# STMF1.net
KiCad netlist of a schematic drawn in Altium Designer
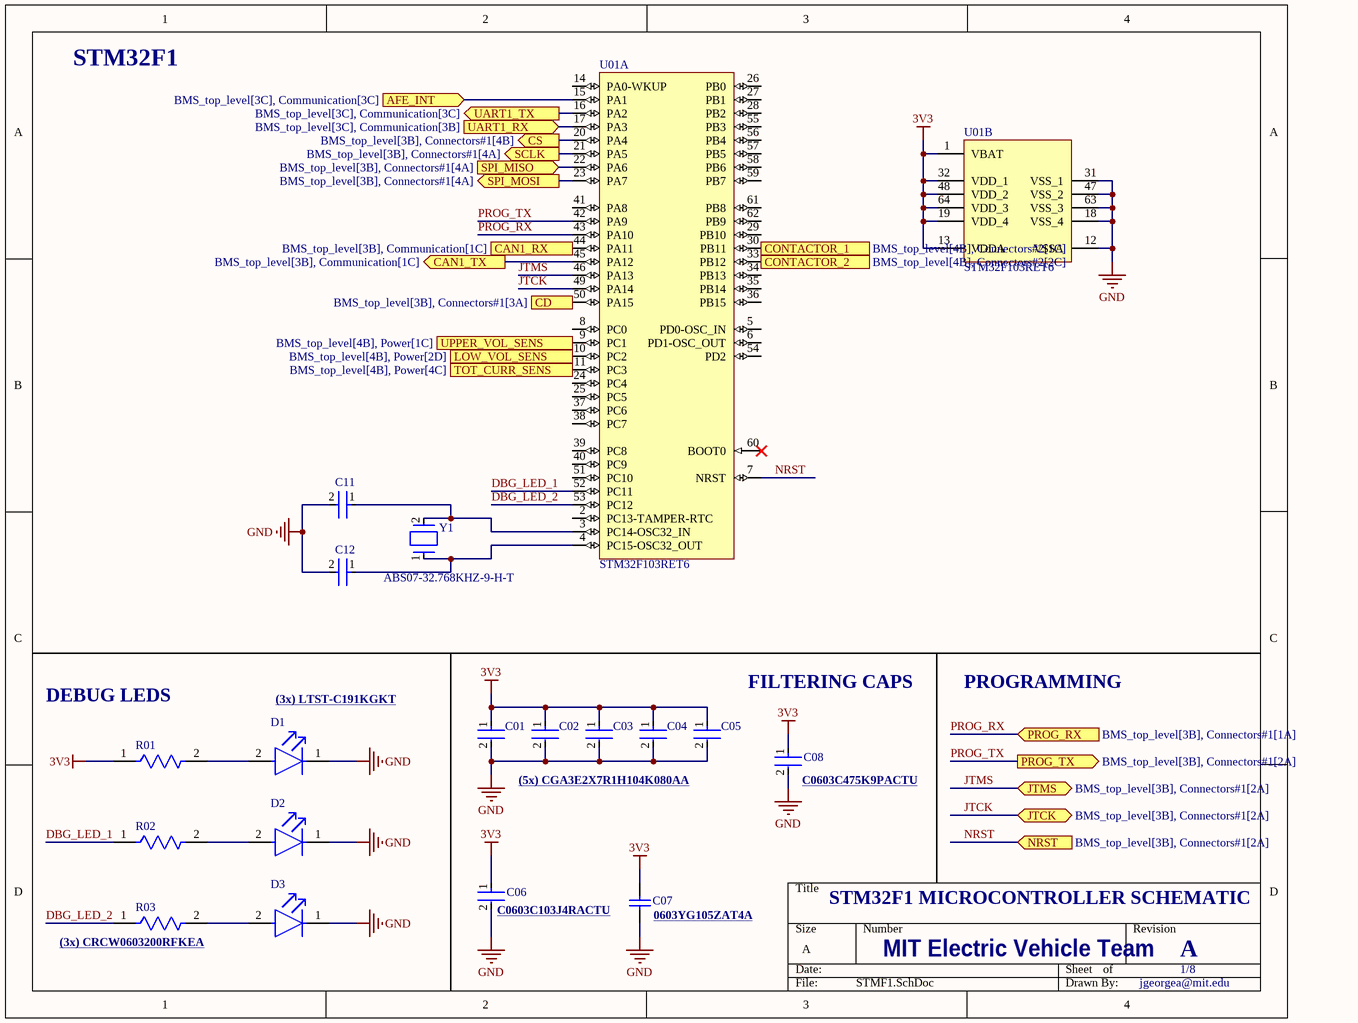
[diagram p0: STMF1.SchDoc]

(export (version "E")
  (design (tool "Eeschema 10.0.6"))
  (components
    (comp (ref "C01")
      (value "CGA3E2X7R1H104K080AA")
      (footprint "FP-CGA3E-0_3-0_1-IPC_A")
      (description "Cap Ceramic 100nF 50V X7R 10% Pad SMD 0603 +125°C Automotive T/R")
      (fields (field (name "TOLERANCE") "10%") (field (name "VOLTAGE") "50V"))
      (libsource (lib "Altium Content Vault") (part "b4654b650e69147ec39a6b967a45e02"))
    )
    (comp (ref "C02")
      (value "CGA3E2X7R1H104K080AA")
      (footprint "FP-CGA3E-0_3-0_1-IPC_A")
      (description "Cap Ceramic 100nF 50V X7R 10% Pad SMD 0603 +125°C Automotive T/R")
      (fields (field (name "TOLERANCE") "10%") (field (name "VOLTAGE") "50V"))
      (libsource (lib "Altium Content Vault") (part "b4654b650e69147ec39a6b967a45e02"))
    )
    (comp (ref "C03")
      (value "CGA3E2X7R1H104K080AA")
      (footprint "FP-CGA3E-0_3-0_1-IPC_A")
      (description "Cap Ceramic 100nF 50V X7R 10% Pad SMD 0603 +125°C Automotive T/R")
      (fields (field (name "TOLERANCE") "10%") (field (name "VOLTAGE") "50V"))
      (libsource (lib "Altium Content Vault") (part "b4654b650e69147ec39a6b967a45e02"))
    )
    (comp (ref "C04")
      (value "CGA3E2X7R1H104K080AA")
      (footprint "FP-CGA3E-0_3-0_1-IPC_A")
      (description "Cap Ceramic 100nF 50V X7R 10% Pad SMD 0603 +125°C Automotive T/R")
      (fields (field (name "TOLERANCE") "10%") (field (name "VOLTAGE") "50V"))
      (libsource (lib "Altium Content Vault") (part "b4654b650e69147ec39a6b967a45e02"))
    )
    (comp (ref "C05")
      (value "CGA3E2X7R1H104K080AA")
      (footprint "FP-CGA3E-0_3-0_1-IPC_A")
      (description "Cap Ceramic 100nF 50V X7R 10% Pad SMD 0603 +125°C Automotive T/R")
      (fields (field (name "TOLERANCE") "10%") (field (name "VOLTAGE") "50V"))
      (libsource (lib "Altium Content Vault") (part "b4654b650e69147ec39a6b967a45e02"))
    )
    (comp (ref "C06")
      (value "C0603C103J4RACTU")
      (footprint "FP-C0603C-CF-MFG")
      (description "CAP CER 10000PF 16V 5% X7R 0603")
      (fields (field (name "TOLERANCE") "0.05") (field (name "MANUFACTURER") "KEMET"))
      (libsource (lib "Altium Content Vault") (part "b4654b650e69147ec39a6b967a45e02"))
    )
    (comp (ref "C07")
      (value "0603YG105ZAT4A")
      (footprint "CAPC1608X90X35ML15T15")
      (fields (field (name "MANUFACTURER") "AVX Interconnect / Elco"))
      (libsource (lib "Altium Content Vault") (part "CAP"))
    )
    (comp (ref "C08")
      (value "C0603C475K9PACTU")
      (footprint "FP-C0603-CG-MFG")
      (description "CAP CER 4.7UF 6.3V X5R 0603")
      (fields (field (name "TOLERANCE") "10%") (field (name "MANUFACTURER") "Kemet"))
      (libsource (lib "Altium Content Vault") (part "11868f565c42a9108669ba33697ecf6"))
    )
    (comp (ref "C11")
      (value "CBR06C409A1GAC")
      (footprint "FP-CBR06C-MFG")
      (description "CAP CER 4PF 100V NP0 0603")
      (fields
        (field (name "MANUFACTURER") "KEMET")
        (field (name "OCTOPART") "https://octopart.com/cbr06c409a1gac-kemet-23801648")
      )
      (libsource (lib "Altium Content Vault") (part "11868f565c42a9108669ba33697ecf6"))
    )
    (comp (ref "C12")
      (value "CBR06C409A1GAC")
      (footprint "FP-CBR06C-MFG")
      (description "CAP CER 4PF 100V NP0 0603")
      (fields
        (field (name "MANUFACTURER") "KEMET")
        (field (name "OCTOPART") "https://octopart.com/cbr06c409a1gac-kemet-23801648")
      )
      (libsource (lib "Altium Content Vault") (part "11868f565c42a9108669ba33697ecf6"))
    )
    (comp (ref "D1")
      (value "LTST-C191KGKT")
      (footprint "FP-LTST-C191KGKT-MFG")
      (description "LED GREEN CLEAR SMD")
      (libsource (lib "Altium Content Vault") (part "8706943c75ba83719d021d2fdc84c58"))
    )
    (comp (ref "D2")
      (value "LTST-C191KGKT")
      (footprint "FP-LTST-C191KGKT-MFG")
      (description "LED GREEN CLEAR SMD")
      (libsource (lib "Altium Content Vault") (part "8706943c75ba83719d021d2fdc84c58"))
    )
    (comp (ref "D3")
      (value "LTST-C191KGKT")
      (footprint "FP-LTST-C191KGKT-MFG")
      (description "LED GREEN CLEAR SMD")
      (libsource (lib "Altium Content Vault") (part "8706943c75ba83719d021d2fdc84c58"))
    )
    (comp (ref "R01")
      (value "CRCW0603200RFKEA")
      (footprint "FP-CRCW0603-e3-MFG")
      (description "RES Thick Film, 200Ω, 1%, 0.1W, 100ppm/°C, 0603")
      (fields (field (name "TOLERANCE") "1%"))
      (libsource (lib "Altium Content Vault") (part "1029c3af85768c4190bb7ad29bc67b5"))
    )
    (comp (ref "R02")
      (value "CRCW0603200RFKEA")
      (footprint "FP-CRCW0603-e3-MFG")
      (description "RES Thick Film, 200Ω, 1%, 0.1W, 100ppm/°C, 0603")
      (fields (field (name "TOLERANCE") "1%"))
      (libsource (lib "Altium Content Vault") (part "1029c3af85768c4190bb7ad29bc67b5"))
    )
    (comp (ref "R03")
      (value "CRCW0603200RFKEA")
      (footprint "FP-CRCW0603-e3-MFG")
      (description "RES Thick Film, 200Ω, 1%, 0.1W, 100ppm/°C, 0603")
      (fields (field (name "TOLERANCE") "1%"))
      (libsource (lib "Altium Content Vault") (part "1029c3af85768c4190bb7ad29bc67b5"))
    )
    (comp (ref "U01")
      (value "STM32F103RET6")
      (footprint "STM-LQFP64_L")
      (libsource (lib "Altium Content Vault") (part "MC-ARM-STM32F103XC_D_E-SQ64"))
    )
    (comp (ref "Y1")
      (value "ABS07-32.768KHZ-9-H-T")
      (footprint "FP-ABS07-MFG")
      (description "Crystal 32.768kHz ±20ppm (Tol) 9pF FUND 70kΩ 2-Pin CSMD T/R")
      (libsource (lib "Altium Content Vault") (part "c23a69dc6c9e2f18f2079038eb95dd1"))
    )
  )
  (nets
    (net (code "1") (name "/AFE_INT") (class "Default")
      (node (ref "U01") (pin "15") (pinfunction "PA1_15") (pintype "bidirectional"))
    )
    (net (code "2") (name "/CAN1_RX") (class "Default")
      (node (ref "U01") (pin "44") (pinfunction "PA11_44") (pintype "bidirectional"))
    )
    (net (code "3") (name "/CAN1_TX") (class "Default")
      (node (ref "U01") (pin "45") (pinfunction "PA12_45") (pintype "bidirectional"))
    )
    (net (code "4") (name "/CD") (class "Default")
      (node (ref "U01") (pin "50") (pinfunction "PA15_50") (pintype "bidirectional"))
    )
    (net (code "5") (name "/CONTACTOR_1") (class "Default")
      (node (ref "U01") (pin "30") (pinfunction "PB11_30") (pintype "bidirectional"))
    )
    (net (code "6") (name "/CONTACTOR_2") (class "Default")
      (node (ref "U01") (pin "33") (pinfunction "PB12_33") (pintype "bidirectional"))
    )
    (net (code "7") (name "/CS") (class "Default")
      (node (ref "U01") (pin "20") (pinfunction "PA4_20") (pintype "bidirectional"))
    )
    (net (code "8") (name "/DBG_LED_1") (class "Default")
      (node (ref "R02") (pin "1") (pinfunction "1_1") (pintype "passive"))
      (node (ref "U01") (pin "52") (pinfunction "PC11_52") (pintype "bidirectional"))
    )
    (net (code "9") (name "/DBG_LED_2") (class "Default")
      (node (ref "R03") (pin "1") (pinfunction "1_1") (pintype "passive"))
      (node (ref "U01") (pin "53") (pinfunction "PC12_53") (pintype "bidirectional"))
    )
    (net (code "10") (name "/JTCK") (class "Default")
      (node (ref "U01") (pin "49") (pinfunction "PA14_49") (pintype "bidirectional"))
    )
    (net (code "11") (name "/JTMS") (class "Default")
      (node (ref "U01") (pin "46") (pinfunction "PA13_46") (pintype "bidirectional"))
    )
    (net (code "12") (name "/LOW_VOL_SENS") (class "Default")
      (node (ref "U01") (pin "10") (pinfunction "PC2_10") (pintype "bidirectional"))
    )
    (net (code "13") (name "/NRST") (class "Default")
      (node (ref "U01") (pin "7") (pinfunction "NRST_7") (pintype "bidirectional"))
    )
    (net (code "14") (name "/PROG_RX") (class "Default")
      (node (ref "U01") (pin "43") (pinfunction "PA10_43") (pintype "bidirectional"))
    )
    (net (code "15") (name "/PROG_TX") (class "Default")
      (node (ref "U01") (pin "42") (pinfunction "PA9_42") (pintype "bidirectional"))
    )
    (net (code "16") (name "/SCLK") (class "Default")
      (node (ref "U01") (pin "21") (pinfunction "PA5_21") (pintype "bidirectional"))
    )
    (net (code "17") (name "/SPI_MISO") (class "Default")
      (node (ref "U01") (pin "22") (pinfunction "PA6_22") (pintype "bidirectional"))
    )
    (net (code "18") (name "/SPI_MOSI") (class "Default")
      (node (ref "U01") (pin "23") (pinfunction "PA7_23") (pintype "bidirectional"))
    )
    (net (code "19") (name "/TOT_CURR_SENS") (class "Default")
      (node (ref "U01") (pin "11") (pinfunction "PC3_11") (pintype "bidirectional"))
    )
    (net (code "20") (name "/UART1_RX") (class "Default")
      (node (ref "U01") (pin "17") (pinfunction "PA3_17") (pintype "bidirectional"))
    )
    (net (code "21") (name "/UART1_TX") (class "Default")
      (node (ref "U01") (pin "16") (pinfunction "PA2_16") (pintype "bidirectional"))
    )
    (net (code "22") (name "/UPPER_VOL_SENS") (class "Default")
      (node (ref "U01") (pin "9") (pinfunction "PC1_9") (pintype "bidirectional"))
    )
    (net (code "23") (name "3V3") (class "Default")
      (node (ref "C01") (pin "1") (pinfunction "1_1") (pintype "passive"))
      (node (ref "C02") (pin "1") (pinfunction "1_1") (pintype "passive"))
      (node (ref "C03") (pin "1") (pinfunction "1_1") (pintype "passive"))
      (node (ref "C04") (pin "1") (pinfunction "1_1") (pintype "passive"))
      (node (ref "C05") (pin "1") (pinfunction "1_1") (pintype "passive"))
      (node (ref "C06") (pin "1") (pinfunction "1_1") (pintype "passive"))
      (node (ref "C07") (pin "2") (pinfunction "2_2") (pintype "passive"))
      (node (ref "C08") (pin "1") (pinfunction "1_1") (pintype "passive"))
      (node (ref "R01") (pin "1") (pinfunction "1_1") (pintype "passive"))
      (node (ref "U01") (pin "1") (pinfunction "VBAT_1") (pintype "power_in"))
      (node (ref "U01") (pin "13") (pinfunction "VDDA_13") (pintype "power_in"))
      (node (ref "U01") (pin "19") (pinfunction "VDD_4_19") (pintype "power_in"))
      (node (ref "U01") (pin "32") (pinfunction "VDD_1_32") (pintype "power_in"))
      (node (ref "U01") (pin "48") (pinfunction "VDD_2_48") (pintype "power_in"))
      (node (ref "U01") (pin "64") (pinfunction "VDD_3_64") (pintype "power_in"))
    )
    (net (code "24") (name "GND") (class "Default")
      (node (ref "C01") (pin "2") (pinfunction "2_2") (pintype "passive"))
      (node (ref "C02") (pin "2") (pinfunction "2_2") (pintype "passive"))
      (node (ref "C03") (pin "2") (pinfunction "2_2") (pintype "passive"))
      (node (ref "C04") (pin "2") (pinfunction "2_2") (pintype "passive"))
      (node (ref "C05") (pin "2") (pinfunction "2_2") (pintype "passive"))
      (node (ref "C06") (pin "2") (pinfunction "2_2") (pintype "passive"))
      (node (ref "C07") (pin "1") (pinfunction "1_1") (pintype "passive"))
      (node (ref "C08") (pin "2") (pinfunction "2_2") (pintype "passive"))
      (node (ref "C11") (pin "2") (pinfunction "2_2") (pintype "passive"))
      (node (ref "C12") (pin "2") (pinfunction "2_2") (pintype "passive"))
      (node (ref "D1") (pin "1") (pinfunction "C_1") (pintype "passive"))
      (node (ref "D2") (pin "1") (pinfunction "C_1") (pintype "passive"))
      (node (ref "D3") (pin "1") (pinfunction "C_1") (pintype "passive"))
      (node (ref "U01") (pin "12") (pinfunction "VSSA_12") (pintype "power_in"))
      (node (ref "U01") (pin "18") (pinfunction "VSS_4_18") (pintype "power_in"))
      (node (ref "U01") (pin "31") (pinfunction "VSS_1_31") (pintype "power_in"))
      (node (ref "U01") (pin "47") (pinfunction "VSS_2_47") (pintype "power_in"))
      (node (ref "U01") (pin "63") (pinfunction "VSS_3_63") (pintype "power_in"))
    )
    (net (code "25") (name "Net-(D1-A)") (class "Default")
      (node (ref "D1") (pin "2") (pinfunction "A_2") (pintype "passive"))
      (node (ref "R01") (pin "2") (pinfunction "2_2") (pintype "passive"))
    )
    (net (code "26") (name "Net-(D2-A)") (class "Default")
      (node (ref "D2") (pin "2") (pinfunction "A_2") (pintype "passive"))
      (node (ref "R02") (pin "2") (pinfunction "2_2") (pintype "passive"))
    )
    (net (code "27") (name "Net-(D3-A)") (class "Default")
      (node (ref "D3") (pin "2") (pinfunction "A_2") (pintype "passive"))
      (node (ref "R03") (pin "2") (pinfunction "2_2") (pintype "passive"))
    )
    (net (code "28") (name "Net-(U01A-PC14-OSC32_IN)") (class "Default")
      (node (ref "C11") (pin "1") (pinfunction "1_1") (pintype "passive"))
      (node (ref "U01") (pin "3") (pinfunction "PC14-OSC32_IN_3") (pintype "bidirectional"))
      (node (ref "Y1") (pin "2") (pinfunction "2_2") (pintype "passive"))
    )
    (net (code "29") (name "Net-(U01A-PC15-OSC32_OUT)") (class "Default")
      (node (ref "C12") (pin "1") (pinfunction "1_1") (pintype "passive"))
      (node (ref "U01") (pin "4") (pinfunction "PC15-OSC32_OUT_4") (pintype "bidirectional"))
      (node (ref "Y1") (pin "1") (pinfunction "1_1") (pintype "passive"))
    )
    (net (code "30") (name "unconnected-(U01A-BOOT0-Pad60)") (class "Default")
      (node (ref "U01") (pin "60") (pinfunction "BOOT0_60") (pintype "input+no_connect"))
    )
    (net (code "31") (name "unconnected-(U01A-PA0-WKUP-Pad14)") (class "Default")
      (node (ref "U01") (pin "14") (pinfunction "PA0-WKUP_14") (pintype "bidirectional"))
    )
    (net (code "32") (name "unconnected-(U01A-PA8-Pad41)") (class "Default")
      (node (ref "U01") (pin "41") (pinfunction "PA8_41") (pintype "bidirectional"))
    )
    (net (code "33") (name "unconnected-(U01A-PB0-Pad26)") (class "Default")
      (node (ref "U01") (pin "26") (pinfunction "PB0_26") (pintype "bidirectional"))
    )
    (net (code "34") (name "unconnected-(U01A-PB1-Pad27)") (class "Default")
      (node (ref "U01") (pin "27") (pinfunction "PB1_27") (pintype "bidirectional"))
    )
    (net (code "35") (name "unconnected-(U01A-PB2-Pad28)") (class "Default")
      (node (ref "U01") (pin "28") (pinfunction "PB2_28") (pintype "bidirectional"))
    )
    (net (code "36") (name "unconnected-(U01A-PB3-Pad55)") (class "Default")
      (node (ref "U01") (pin "55") (pinfunction "PB3_55") (pintype "bidirectional"))
    )
    (net (code "37") (name "unconnected-(U01A-PB4-Pad56)") (class "Default")
      (node (ref "U01") (pin "56") (pinfunction "PB4_56") (pintype "bidirectional"))
    )
    (net (code "38") (name "unconnected-(U01A-PB5-Pad57)") (class "Default")
      (node (ref "U01") (pin "57") (pinfunction "PB5_57") (pintype "bidirectional"))
    )
    (net (code "39") (name "unconnected-(U01A-PB6-Pad58)") (class "Default")
      (node (ref "U01") (pin "58") (pinfunction "PB6_58") (pintype "bidirectional"))
    )
    (net (code "40") (name "unconnected-(U01A-PB7-Pad59)") (class "Default")
      (node (ref "U01") (pin "59") (pinfunction "PB7_59") (pintype "bidirectional"))
    )
    (net (code "41") (name "unconnected-(U01A-PB8-Pad61)") (class "Default")
      (node (ref "U01") (pin "61") (pinfunction "PB8_61") (pintype "bidirectional"))
    )
    (net (code "42") (name "unconnected-(U01A-PB9-Pad62)") (class "Default")
      (node (ref "U01") (pin "62") (pinfunction "PB9_62") (pintype "bidirectional"))
    )
    (net (code "43") (name "unconnected-(U01A-PB10-Pad29)") (class "Default")
      (node (ref "U01") (pin "29") (pinfunction "PB10_29") (pintype "bidirectional"))
    )
    (net (code "44") (name "unconnected-(U01A-PB13-Pad34)") (class "Default")
      (node (ref "U01") (pin "34") (pinfunction "PB13_34") (pintype "bidirectional"))
    )
    (net (code "45") (name "unconnected-(U01A-PB14-Pad35)") (class "Default")
      (node (ref "U01") (pin "35") (pinfunction "PB14_35") (pintype "bidirectional"))
    )
    (net (code "46") (name "unconnected-(U01A-PB15-Pad36)") (class "Default")
      (node (ref "U01") (pin "36") (pinfunction "PB15_36") (pintype "bidirectional"))
    )
    (net (code "47") (name "unconnected-(U01A-PC0-Pad8)") (class "Default")
      (node (ref "U01") (pin "8") (pinfunction "PC0_8") (pintype "bidirectional"))
    )
    (net (code "48") (name "unconnected-(U01A-PC4-Pad24)") (class "Default")
      (node (ref "U01") (pin "24") (pinfunction "PC4_24") (pintype "bidirectional"))
    )
    (net (code "49") (name "unconnected-(U01A-PC5-Pad25)") (class "Default")
      (node (ref "U01") (pin "25") (pinfunction "PC5_25") (pintype "bidirectional"))
    )
    (net (code "50") (name "unconnected-(U01A-PC6-Pad37)") (class "Default")
      (node (ref "U01") (pin "37") (pinfunction "PC6_37") (pintype "bidirectional"))
    )
    (net (code "51") (name "unconnected-(U01A-PC7-Pad38)") (class "Default")
      (node (ref "U01") (pin "38") (pinfunction "PC7_38") (pintype "bidirectional"))
    )
    (net (code "52") (name "unconnected-(U01A-PC8-Pad39)") (class "Default")
      (node (ref "U01") (pin "39") (pinfunction "PC8_39") (pintype "bidirectional"))
    )
    (net (code "53") (name "unconnected-(U01A-PC9-Pad40)") (class "Default")
      (node (ref "U01") (pin "40") (pinfunction "PC9_40") (pintype "bidirectional"))
    )
    (net (code "54") (name "unconnected-(U01A-PC10-Pad51)") (class "Default")
      (node (ref "U01") (pin "51") (pinfunction "PC10_51") (pintype "bidirectional"))
    )
    (net (code "55") (name "unconnected-(U01A-PC13-TAMPER-RTC-Pad2)") (class "Default")
      (node (ref "U01") (pin "2") (pinfunction "PC13-TAMPER-RTC_2") (pintype "bidirectional"))
    )
    (net (code "56") (name "unconnected-(U01A-PD0-OSC_IN-Pad5)") (class "Default")
      (node (ref "U01") (pin "5") (pinfunction "PD0-OSC_IN_5") (pintype "bidirectional"))
    )
    (net (code "57") (name "unconnected-(U01A-PD1-OSC_OUT-Pad6)") (class "Default")
      (node (ref "U01") (pin "6") (pinfunction "PD1-OSC_OUT_6") (pintype "bidirectional"))
    )
    (net (code "58") (name "unconnected-(U01A-PD2-Pad54)") (class "Default")
      (node (ref "U01") (pin "54") (pinfunction "PD2_54") (pintype "bidirectional"))
    )
  )
)
